# M452A.net
KiCad netlist of a schematic drawn in EAGLE
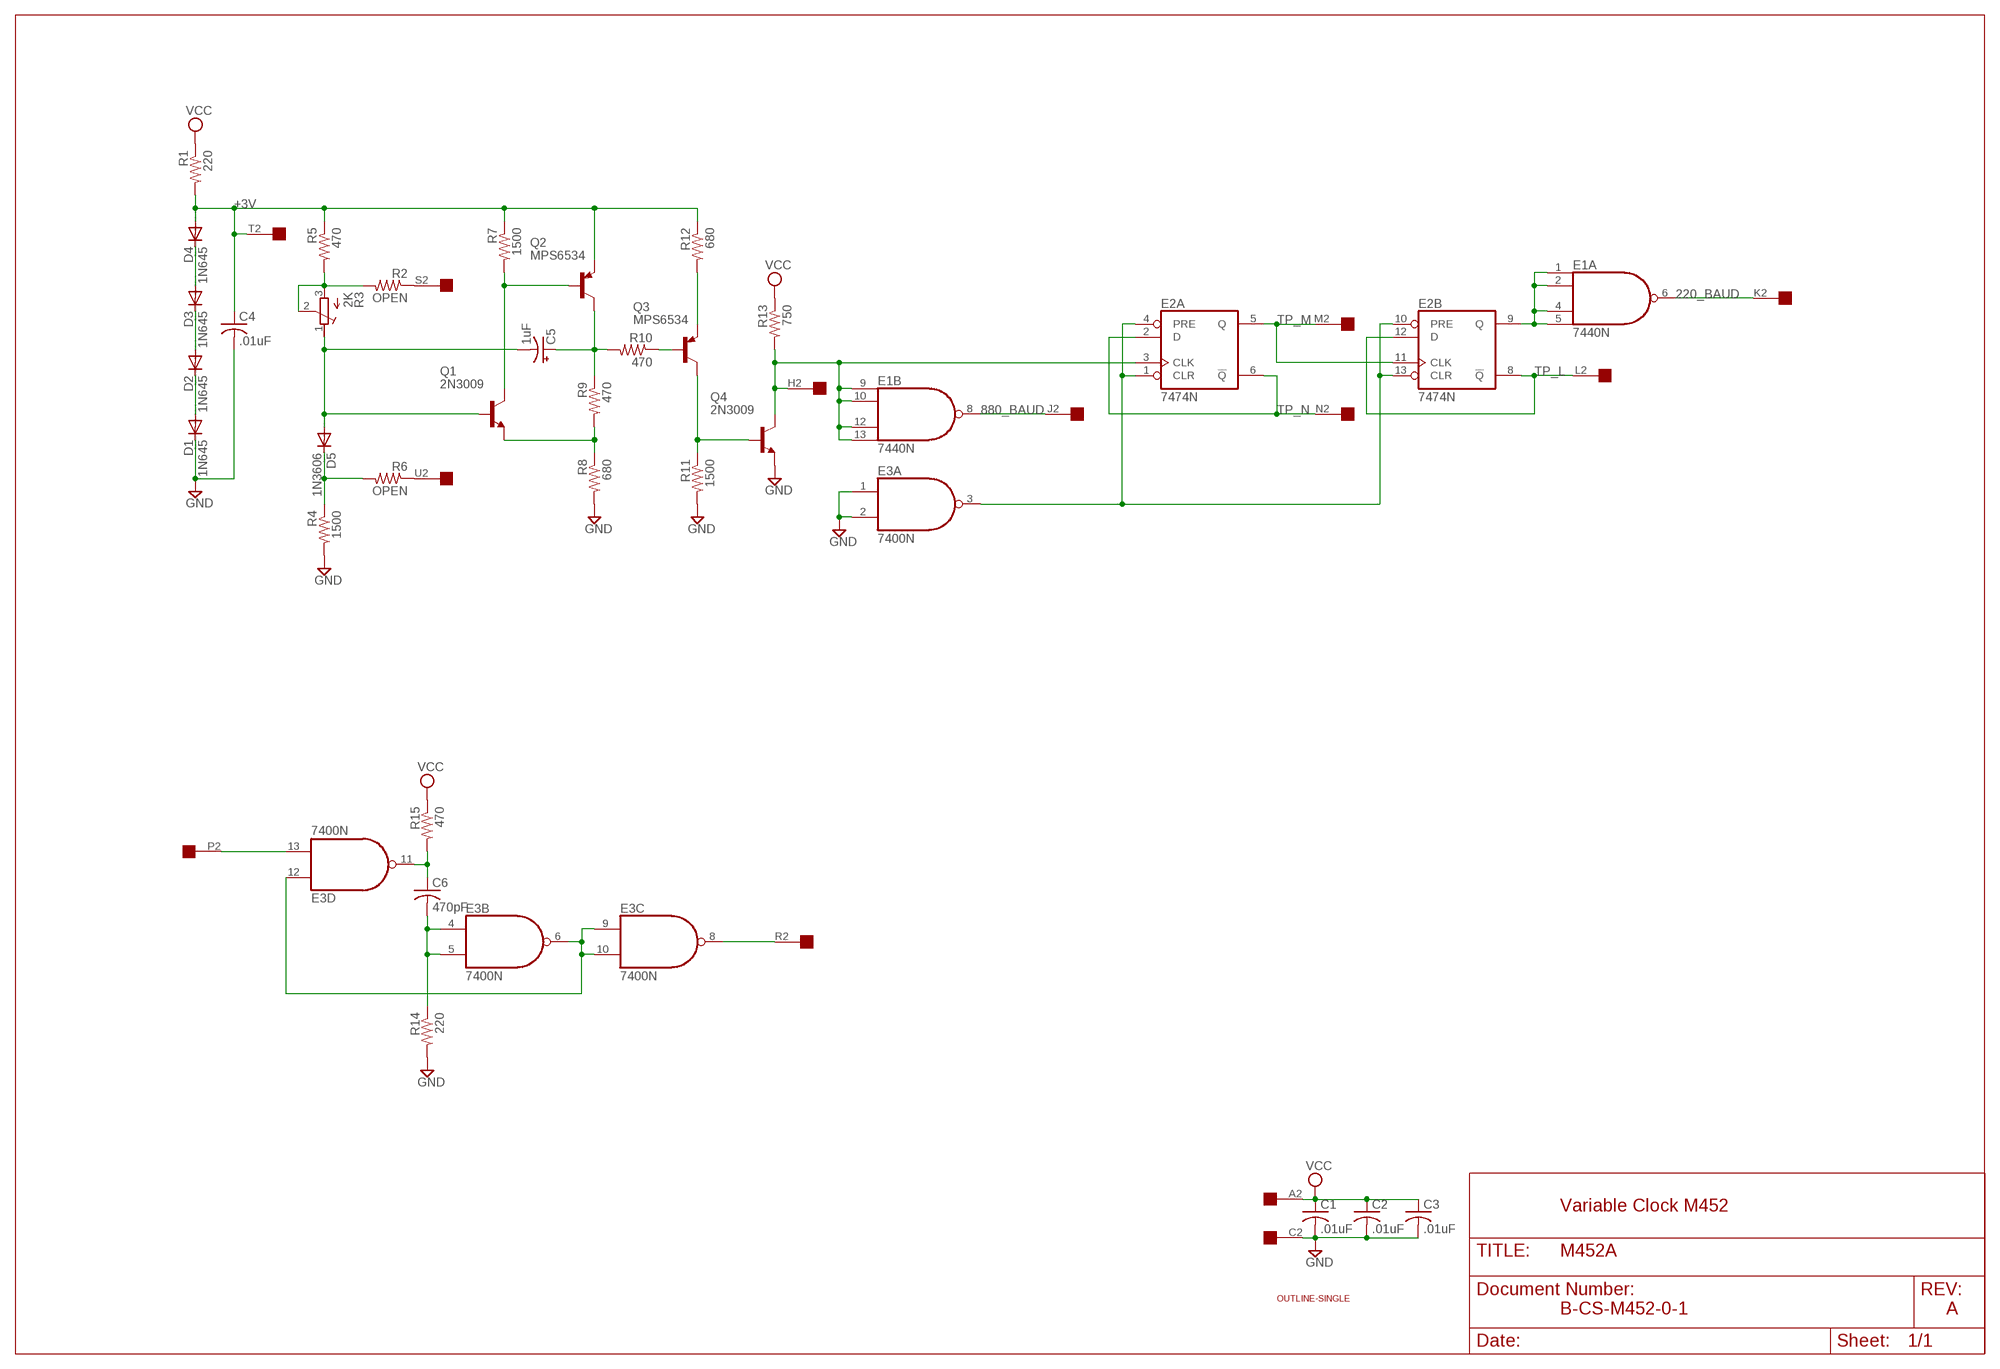
[diagram p0: schematic, sheet 1]

(export (version "E")
  (design (tool "Eeschema 10.0.6"))
  (components
    (comp (ref "C1")
      (value ".01uF")
      (footprint "eagle-import:C050-025X075")
      (libsource (lib "eagle-import") (part "C-US050-025X075"))
    )
    (comp (ref "C2")
      (value ".01uF")
      (footprint "eagle-import:C050-025X075")
      (libsource (lib "eagle-import") (part "C-US050-025X075"))
    )
    (comp (ref "C3")
      (value ".01uF")
      (footprint "eagle-import:C050-025X075")
      (libsource (lib "eagle-import") (part "C-US050-025X075"))
    )
    (comp (ref "C4")
      (value ".01uF")
      (footprint "eagle-import:C050-025X075")
      (libsource (lib "eagle-import") (part "C-US050-025X075"))
    )
    (comp (ref "C5")
      (value "1uF")
      (footprint "eagle-import:E15-5")
      (libsource (lib "eagle-import") (part "CPOL-USE15-5AXIAL"))
    )
    (comp (ref "C6")
      (value "470pF")
      (footprint "eagle-import:C150-054X183")
      (libsource (lib "eagle-import") (part "C-US150-054X183"))
    )
    (comp (ref "D1")
      (value "1N645")
      (footprint "eagle-import:DO35-10")
      (libsource (lib "eagle-import") (part "1N4148DO35-10"))
    )
    (comp (ref "D2")
      (value "1N645")
      (footprint "eagle-import:DO35-10")
      (libsource (lib "eagle-import") (part "1N4148DO35-10"))
    )
    (comp (ref "D3")
      (value "1N645")
      (footprint "eagle-import:DO35-10")
      (libsource (lib "eagle-import") (part "1N4148DO35-10"))
    )
    (comp (ref "D4")
      (value "1N645")
      (footprint "eagle-import:DO35-10")
      (libsource (lib "eagle-import") (part "1N4148DO35-10"))
    )
    (comp (ref "D5")
      (value "1N3606")
      (footprint "eagle-import:DO35-10")
      (libsource (lib "eagle-import") (part "1N4148DO35-10"))
    )
    (comp (ref "E1")
      (value "7440N")
      (footprint "eagle-import:DIL14")
      (libsource (lib "eagle-import") (part "7420NS"))
    )
    (comp (ref "E2")
      (value "7474N")
      (footprint "eagle-import:DIL14")
      (libsource (lib "eagle-import") (part "7474NS"))
    )
    (comp (ref "E3")
      (value "7400N")
      (footprint "eagle-import:DIL14")
      (libsource (lib "eagle-import") (part "7400N"))
    )
    (comp (ref "Q1")
      (value "2N3009")
      (footprint "eagle-import:TO39")
      (libsource (lib "eagle-import") (part "-NPN-TO39-EBC2N3019"))
    )
    (comp (ref "Q2")
      (value "MPS6534")
      (footprint "eagle-import:TO39")
      (libsource (lib "eagle-import") (part "-PNP-TO39-EBC2N3637"))
    )
    (comp (ref "Q3")
      (value "MPS6534")
      (footprint "eagle-import:TO39")
      (libsource (lib "eagle-import") (part "-PNP-TO39-EBC2N3637"))
    )
    (comp (ref "Q4")
      (value "2N3009")
      (footprint "eagle-import:TO39")
      (libsource (lib "eagle-import") (part "-NPN-TO39-EBC2N3019"))
    )
    (comp (ref "R1")
      (value "220")
      (footprint "eagle-import:0207_10")
      (libsource (lib "eagle-import") (part "R-US_0207/10"))
    )
    (comp (ref "R2")
      (value "OPEN")
      (footprint "eagle-import:0207_10")
      (libsource (lib "eagle-import") (part "R-US_0207/10"))
    )
    (comp (ref "R3")
      (value "2K")
      (footprint "eagle-import:3006Y")
      (libsource (lib "eagle-import") (part "275P"))
    )
    (comp (ref "R4")
      (value "1500")
      (footprint "eagle-import:0207_10")
      (libsource (lib "eagle-import") (part "R-US_0207/10"))
    )
    (comp (ref "R5")
      (value "470")
      (footprint "eagle-import:0207_10")
      (libsource (lib "eagle-import") (part "R-US_0207/10"))
    )
    (comp (ref "R6")
      (value "OPEN")
      (footprint "eagle-import:0207_10")
      (libsource (lib "eagle-import") (part "R-US_0207/10"))
    )
    (comp (ref "R7")
      (value "1500")
      (footprint "eagle-import:0207_10")
      (libsource (lib "eagle-import") (part "R-US_0207/10"))
    )
    (comp (ref "R8")
      (value "680")
      (footprint "eagle-import:0207_10")
      (libsource (lib "eagle-import") (part "R-US_0207/10"))
    )
    (comp (ref "R9")
      (value "470")
      (footprint "eagle-import:0207_10")
      (libsource (lib "eagle-import") (part "R-US_0207/10"))
    )
    (comp (ref "R10")
      (value "470")
      (footprint "eagle-import:0207_10")
      (libsource (lib "eagle-import") (part "R-US_0207/10"))
    )
    (comp (ref "R11")
      (value "1500")
      (footprint "eagle-import:0207_10")
      (libsource (lib "eagle-import") (part "R-US_0207/10"))
    )
    (comp (ref "R12")
      (value "680")
      (footprint "eagle-import:0207_10")
      (libsource (lib "eagle-import") (part "R-US_0207/10"))
    )
    (comp (ref "R13")
      (value "750")
      (footprint "eagle-import:0207_10")
      (libsource (lib "eagle-import") (part "R-US_0207/10"))
    )
    (comp (ref "R14")
      (value "220")
      (footprint "eagle-import:0207_10")
      (libsource (lib "eagle-import") (part "R-US_0207/10"))
    )
    (comp (ref "R15")
      (value "470")
      (footprint "eagle-import:0207_10")
      (libsource (lib "eagle-import") (part "R-US_0207/10"))
    )
    (comp (ref "U$1")
      (value "OUTLINE-SINGLE")
      (footprint "eagle-import:SINGLE")
      (libsource (lib "eagle-import") (part "OUTLINE-SINGLE"))
    )
    (comp (ref "U$2")
      (value "EDGE-1")
      (footprint "eagle-import:EDGE-CON1")
      (libsource (lib "eagle-import") (part "EDGE-1"))
    )
  )
  (nets
    (net (code "1") (name "/+3V") (class "Default")
      (node (ref "C4") (pin "1") (pinfunction "1_1") (pintype "passive"))
      (node (ref "D4") (pin "A") (pinfunction "A_A") (pintype "passive"))
      (node (ref "Q2") (pin "1") (pinfunction "E_1") (pintype "passive"))
      (node (ref "R1") (pin "2") (pinfunction "2_2") (pintype "passive"))
      (node (ref "R12") (pin "1") (pinfunction "1_1") (pintype "passive"))
      (node (ref "R5") (pin "1") (pinfunction "1_1") (pintype "passive"))
      (node (ref "R7") (pin "1") (pinfunction "1_1") (pintype "passive"))
      (node (ref "U$2") (pin "T2") (pinfunction "1_T2") (pintype "bidirectional"))
    )
    (net (code "2") (name "/220_BAUD") (class "Default")
      (node (ref "E1") (pin "6") (pinfunction "O_6") (pintype "output"))
      (node (ref "U$2") (pin "K2") (pinfunction "1_K2") (pintype "bidirectional"))
    )
    (net (code "3") (name "/880_BAUD") (class "Default")
      (node (ref "E1") (pin "8") (pinfunction "O_8") (pintype "output"))
      (node (ref "U$2") (pin "J2") (pinfunction "1_J2") (pintype "bidirectional"))
    )
    (net (code "4") (name "/TP_L") (class "Default")
      (node (ref "E2") (pin "12") (pinfunction "D_12") (pintype "input"))
      (node (ref "E2") (pin "8") (pinfunction "~{Q}_8") (pintype "output"))
      (node (ref "U$2") (pin "L2") (pinfunction "1_L2") (pintype "bidirectional"))
    )
    (net (code "5") (name "/TP_M") (class "Default")
      (node (ref "E2") (pin "11") (pinfunction "CLK_11") (pintype "input"))
      (node (ref "E2") (pin "5") (pinfunction "Q_5") (pintype "output"))
      (node (ref "U$2") (pin "M2") (pinfunction "1_M2") (pintype "bidirectional"))
    )
    (net (code "6") (name "/TP_N") (class "Default")
      (node (ref "E2") (pin "2") (pinfunction "D_2") (pintype "input"))
      (node (ref "E2") (pin "6") (pinfunction "~{Q}_6") (pintype "output"))
      (node (ref "U$2") (pin "N2") (pinfunction "1_N2") (pintype "bidirectional"))
    )
    (net (code "7") (name "GND") (class "Default")
      (node (ref "C1") (pin "2") (pinfunction "2_2") (pintype "passive"))
      (node (ref "C2") (pin "2") (pinfunction "2_2") (pintype "passive"))
      (node (ref "C3") (pin "2") (pinfunction "2_2") (pintype "passive"))
      (node (ref "C4") (pin "2") (pinfunction "2_2") (pintype "passive"))
      (node (ref "D1") (pin "C") (pinfunction "C_C") (pintype "passive"))
      (node (ref "E3") (pin "1") (pinfunction "I0_1") (pintype "input"))
      (node (ref "E3") (pin "2") (pinfunction "I1_2") (pintype "input"))
      (node (ref "Q4") (pin "1") (pinfunction "E_1") (pintype "passive"))
      (node (ref "R11") (pin "2") (pinfunction "2_2") (pintype "passive"))
      (node (ref "R14") (pin "2") (pinfunction "2_2") (pintype "passive"))
      (node (ref "R4") (pin "2") (pinfunction "2_2") (pintype "passive"))
      (node (ref "R8") (pin "2") (pinfunction "2_2") (pintype "passive"))
      (node (ref "U$2") (pin "C2") (pinfunction "1_C2") (pintype "bidirectional"))
    )
    (net (code "8") (name "Net-(D1-PadA)") (class "Default")
      (node (ref "D1") (pin "A") (pinfunction "A_A") (pintype "passive"))
      (node (ref "D2") (pin "C") (pinfunction "C_C") (pintype "passive"))
    )
    (net (code "9") (name "Net-(D2-PadA)") (class "Default")
      (node (ref "D2") (pin "A") (pinfunction "A_A") (pintype "passive"))
      (node (ref "D3") (pin "C") (pinfunction "C_C") (pintype "passive"))
    )
    (net (code "10") (name "Net-(D3-PadA)") (class "Default")
      (node (ref "D3") (pin "A") (pinfunction "A_A") (pintype "passive"))
      (node (ref "D4") (pin "C") (pinfunction "C_C") (pintype "passive"))
    )
    (net (code "11") (name "Net-(D5-PadC)") (class "Default")
      (node (ref "D5") (pin "C") (pinfunction "C_C") (pintype "passive"))
      (node (ref "R4") (pin "1") (pinfunction "1_1") (pintype "passive"))
      (node (ref "R6") (pin "2") (pinfunction "2_2") (pintype "passive"))
    )
    (net (code "12") (name "Net-(E1A-I0)") (class "Default")
      (node (ref "E1") (pin "1") (pinfunction "I0_1") (pintype "input"))
      (node (ref "E1") (pin "2") (pinfunction "I1_2") (pintype "input"))
      (node (ref "E1") (pin "4") (pinfunction "I2_4") (pintype "input"))
      (node (ref "E1") (pin "5") (pinfunction "I3_5") (pintype "input"))
      (node (ref "E2") (pin "9") (pinfunction "Q_9") (pintype "output"))
    )
    (net (code "13") (name "Net-(E1B-I0)") (class "Default")
      (node (ref "E1") (pin "10") (pinfunction "I1_10") (pintype "input"))
      (node (ref "E1") (pin "12") (pinfunction "I2_12") (pintype "input"))
      (node (ref "E1") (pin "13") (pinfunction "I3_13") (pintype "input"))
      (node (ref "E1") (pin "9") (pinfunction "I0_9") (pintype "input"))
      (node (ref "E2") (pin "3") (pinfunction "CLK_3") (pintype "input"))
      (node (ref "Q4") (pin "3") (pinfunction "C_3") (pintype "passive"))
      (node (ref "R13") (pin "2") (pinfunction "2_2") (pintype "passive"))
      (node (ref "U$2") (pin "H2") (pinfunction "1_H2") (pintype "bidirectional"))
    )
    (net (code "14") (name "Net-(E2A-CLR)") (class "Default")
      (node (ref "E2") (pin "1") (pinfunction "CLR_1") (pintype "input"))
      (node (ref "E2") (pin "10") (pinfunction "PRE_10") (pintype "input"))
      (node (ref "E2") (pin "13") (pinfunction "CLR_13") (pintype "input"))
      (node (ref "E2") (pin "4") (pinfunction "PRE_4") (pintype "input"))
      (node (ref "E3") (pin "3") (pinfunction "O_3") (pintype "output"))
    )
    (net (code "15") (name "Net-(E3B-I0)") (class "Default")
      (node (ref "C6") (pin "2") (pinfunction "2_2") (pintype "passive"))
      (node (ref "E3") (pin "4") (pinfunction "I0_4") (pintype "input"))
      (node (ref "E3") (pin "5") (pinfunction "I1_5") (pintype "input"))
      (node (ref "R14") (pin "1") (pinfunction "1_1") (pintype "passive"))
    )
    (net (code "16") (name "Net-(E3B-O)") (class "Default")
      (node (ref "E3") (pin "10") (pinfunction "I1_10") (pintype "input"))
      (node (ref "E3") (pin "12") (pinfunction "I0_12") (pintype "input"))
      (node (ref "E3") (pin "6") (pinfunction "O_6") (pintype "output"))
      (node (ref "E3") (pin "9") (pinfunction "I0_9") (pintype "input"))
    )
    (net (code "17") (name "Net-(E3C-O)") (class "Default")
      (node (ref "E3") (pin "8") (pinfunction "O_8") (pintype "output"))
      (node (ref "U$2") (pin "R2") (pinfunction "1_R2") (pintype "bidirectional"))
    )
    (net (code "18") (name "Net-(E3D-I1)") (class "Default")
      (node (ref "E3") (pin "13") (pinfunction "I1_13") (pintype "input"))
      (node (ref "U$2") (pin "P2") (pinfunction "1_P2") (pintype "bidirectional"))
    )
    (net (code "19") (name "Net-(E3D-O)") (class "Default")
      (node (ref "C6") (pin "1") (pinfunction "1_1") (pintype "passive"))
      (node (ref "E3") (pin "11") (pinfunction "O_11") (pintype "output"))
      (node (ref "R15") (pin "2") (pinfunction "2_2") (pintype "passive"))
    )
    (net (code "20") (name "Net-(Q1-B)") (class "Default")
      (node (ref "C5") (pin "-") (pinfunction "-_-") (pintype "passive"))
      (node (ref "D5") (pin "A") (pinfunction "A_A") (pintype "passive"))
      (node (ref "Q1") (pin "2") (pinfunction "B_2") (pintype "passive"))
      (node (ref "R3") (pin "1") (pinfunction "A_1") (pintype "passive"))
    )
    (net (code "21") (name "Net-(Q1-C)") (class "Default")
      (node (ref "Q1") (pin "3") (pinfunction "C_3") (pintype "passive"))
      (node (ref "Q2") (pin "2") (pinfunction "B_2") (pintype "passive"))
      (node (ref "R7") (pin "2") (pinfunction "2_2") (pintype "passive"))
    )
    (net (code "22") (name "Net-(Q1-E)") (class "Default")
      (node (ref "Q1") (pin "1") (pinfunction "E_1") (pintype "passive"))
      (node (ref "R8") (pin "1") (pinfunction "1_1") (pintype "passive"))
      (node (ref "R9") (pin "2") (pinfunction "2_2") (pintype "passive"))
    )
    (net (code "23") (name "Net-(Q2-C)") (class "Default")
      (node (ref "C5") (pin "+") (pinfunction "+_+") (pintype "passive"))
      (node (ref "Q2") (pin "3") (pinfunction "C_3") (pintype "passive"))
      (node (ref "R10") (pin "2") (pinfunction "2_2") (pintype "passive"))
      (node (ref "R9") (pin "1") (pinfunction "1_1") (pintype "passive"))
    )
    (net (code "24") (name "Net-(Q3-B)") (class "Default")
      (node (ref "Q3") (pin "2") (pinfunction "B_2") (pintype "passive"))
      (node (ref "R10") (pin "1") (pinfunction "1_1") (pintype "passive"))
    )
    (net (code "25") (name "Net-(Q3-C)") (class "Default")
      (node (ref "Q3") (pin "3") (pinfunction "C_3") (pintype "passive"))
      (node (ref "Q4") (pin "2") (pinfunction "B_2") (pintype "passive"))
      (node (ref "R11") (pin "1") (pinfunction "1_1") (pintype "passive"))
    )
    (net (code "26") (name "Net-(Q3-E)") (class "Default")
      (node (ref "Q3") (pin "1") (pinfunction "E_1") (pintype "passive"))
      (node (ref "R12") (pin "2") (pinfunction "2_2") (pintype "passive"))
    )
    (net (code "27") (name "Net-(R3-E)") (class "Default")
      (node (ref "R2") (pin "2") (pinfunction "2_2") (pintype "passive"))
      (node (ref "R3") (pin "2") (pinfunction "S_2") (pintype "passive"))
      (node (ref "R3") (pin "3") (pinfunction "E_3") (pintype "passive"))
      (node (ref "R5") (pin "2") (pinfunction "2_2") (pintype "passive"))
    )
    (net (code "28") (name "Net-(U$2O-1)") (class "Default")
      (node (ref "R2") (pin "1") (pinfunction "1_1") (pintype "passive"))
      (node (ref "U$2") (pin "S2") (pinfunction "1_S2") (pintype "bidirectional"))
    )
    (net (code "29") (name "Net-(U$2Q-1)") (class "Default")
      (node (ref "R6") (pin "1") (pinfunction "1_1") (pintype "passive"))
      (node (ref "U$2") (pin "U2") (pinfunction "1_U2") (pintype "bidirectional"))
    )
    (net (code "30") (name "VCC") (class "Default")
      (node (ref "C1") (pin "1") (pinfunction "1_1") (pintype "passive"))
      (node (ref "C2") (pin "1") (pinfunction "1_1") (pintype "passive"))
      (node (ref "C3") (pin "1") (pinfunction "1_1") (pintype "passive"))
      (node (ref "R1") (pin "1") (pinfunction "1_1") (pintype "passive"))
      (node (ref "R13") (pin "1") (pinfunction "1_1") (pintype "passive"))
      (node (ref "R15") (pin "1") (pinfunction "1_1") (pintype "passive"))
      (node (ref "U$2") (pin "A2") (pinfunction "1_A2") (pintype "bidirectional"))
    )
  )
)
